# Development_Board_ATMega32.net
KiCad netlist of a schematic drawn in EAGLE
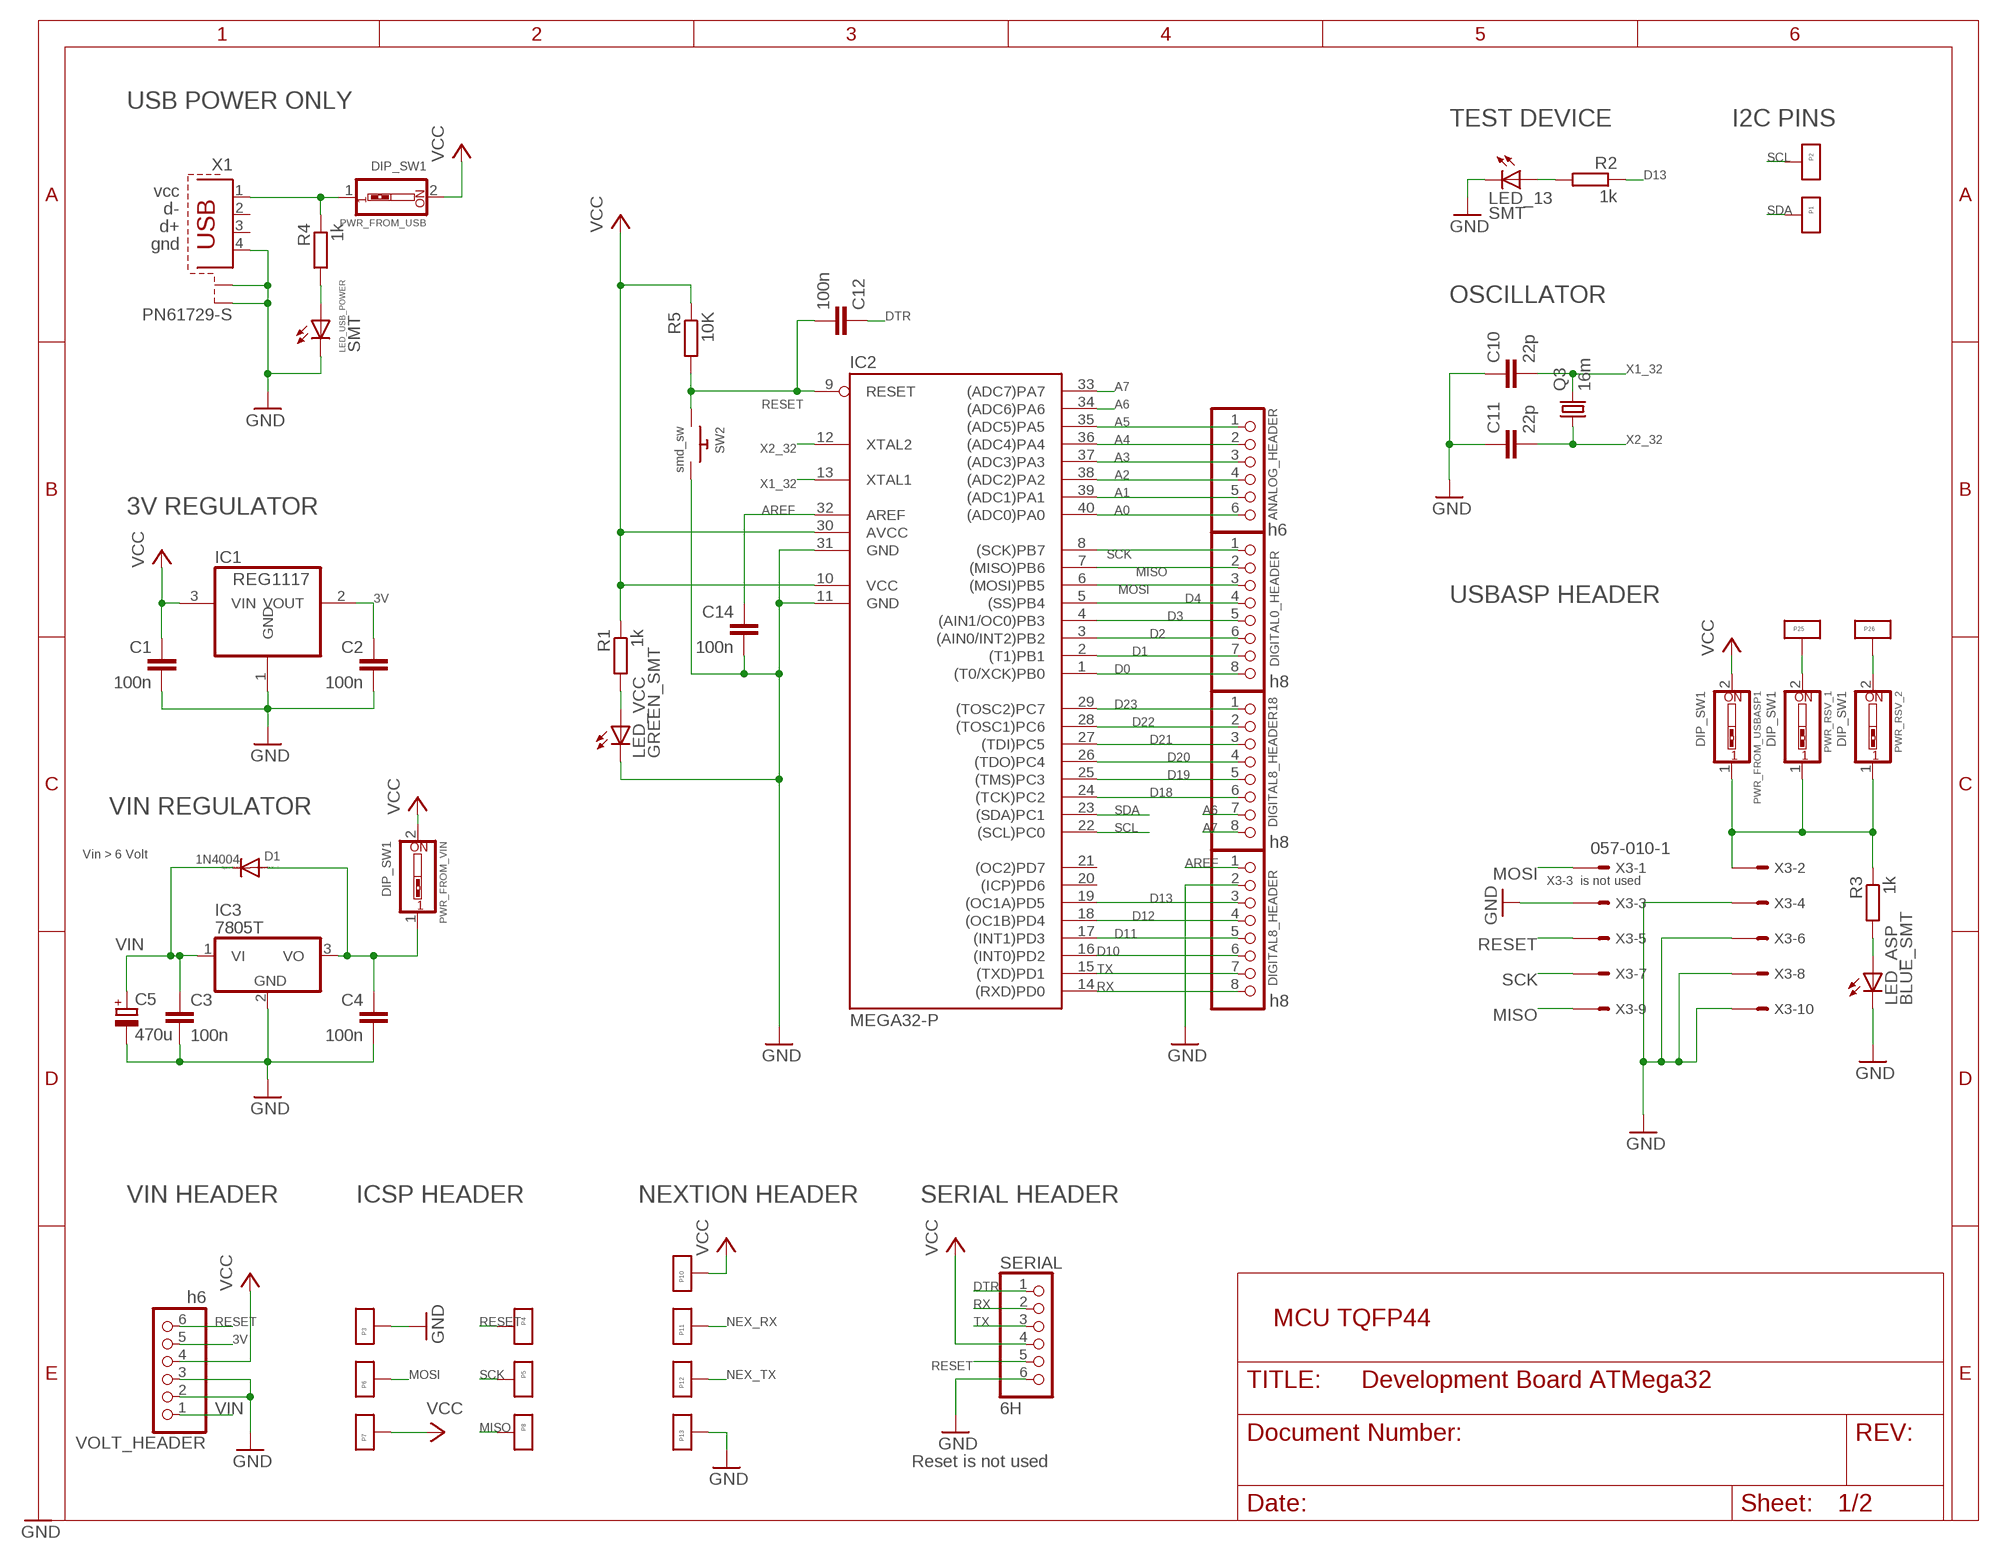
[diagram p0: schematic, sheet 1]
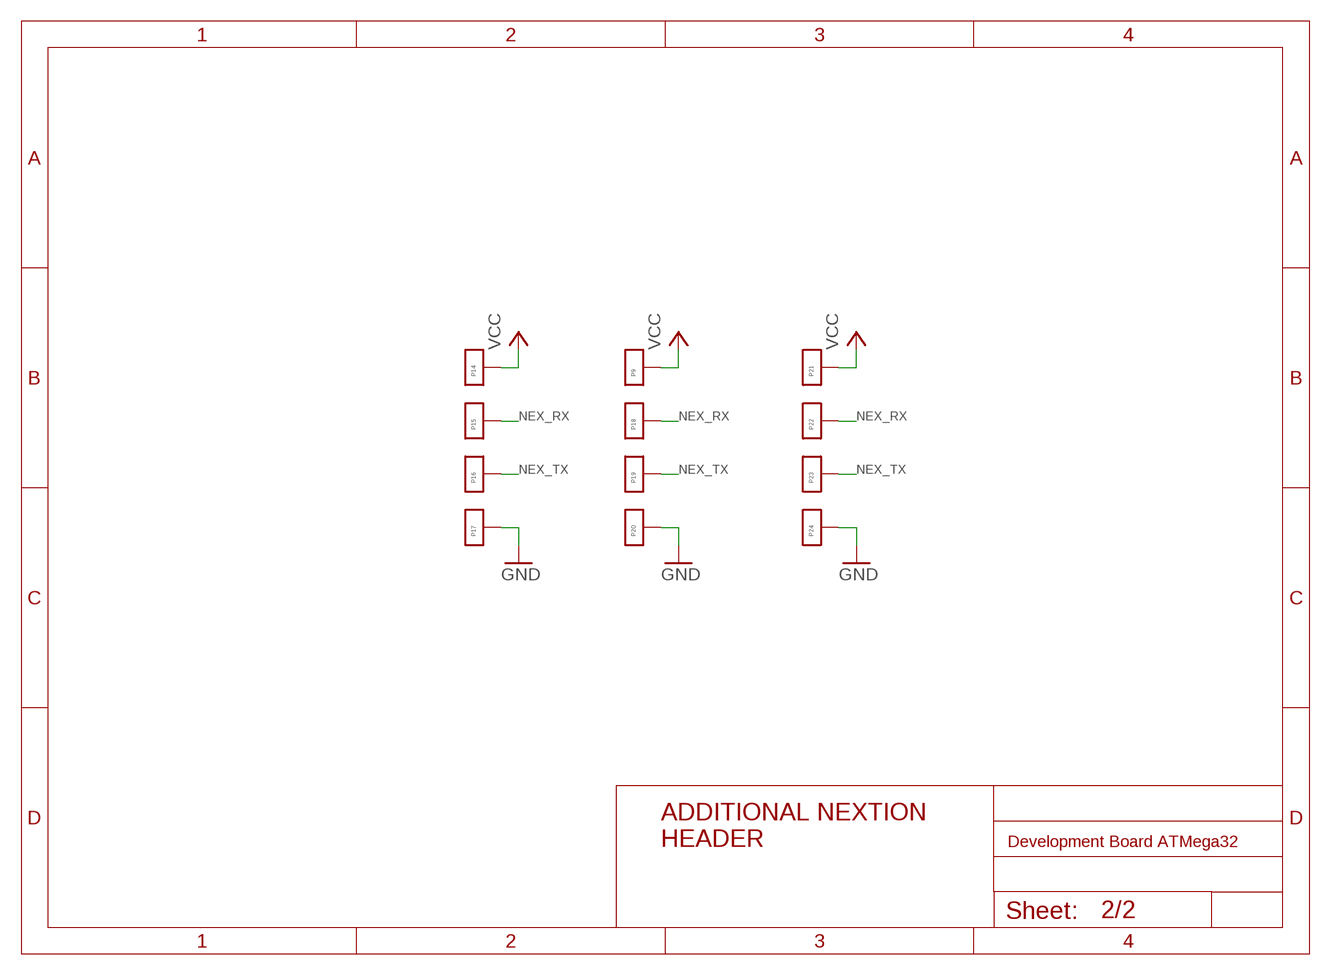
[diagram p1: schematic, sheet 2]

(export (version "E")
  (design (tool "Eeschema 10.0.6"))
  (components
    (comp (ref "P9")
      (value "PIN-BIG1X")
      (footprint "eagle-import:PIN-BIG")
      (libsource (lib "eagle-import") (part "PIN-BIG1X"))
    )
    (comp (ref "P14")
      (value "PIN-BIG1X")
      (footprint "eagle-import:PIN-BIG")
      (libsource (lib "eagle-import") (part "PIN-BIG1X"))
    )
    (comp (ref "P15")
      (value "PIN-BIG1X")
      (footprint "eagle-import:PIN-BIG")
      (libsource (lib "eagle-import") (part "PIN-BIG1X"))
    )
    (comp (ref "P16")
      (value "PIN-BIG1X")
      (footprint "eagle-import:PIN-BIG")
      (libsource (lib "eagle-import") (part "PIN-BIG1X"))
    )
    (comp (ref "P17")
      (value "PIN-BIG1X")
      (footprint "eagle-import:PIN-BIG")
      (libsource (lib "eagle-import") (part "PIN-BIG1X"))
    )
    (comp (ref "P18")
      (value "PIN-BIG1X")
      (footprint "eagle-import:PIN-BIG")
      (libsource (lib "eagle-import") (part "PIN-BIG1X"))
    )
    (comp (ref "P19")
      (value "PIN-BIG1X")
      (footprint "eagle-import:PIN-BIG")
      (libsource (lib "eagle-import") (part "PIN-BIG1X"))
    )
    (comp (ref "P20")
      (value "PIN-BIG1X")
      (footprint "eagle-import:PIN-BIG")
      (libsource (lib "eagle-import") (part "PIN-BIG1X"))
    )
    (comp (ref "P21")
      (value "PIN-BIG1X")
      (footprint "eagle-import:PIN-BIG")
      (libsource (lib "eagle-import") (part "PIN-BIG1X"))
    )
    (comp (ref "P22")
      (value "PIN-BIG1X")
      (footprint "eagle-import:PIN-BIG")
      (libsource (lib "eagle-import") (part "PIN-BIG1X"))
    )
    (comp (ref "P23")
      (value "PIN-BIG1X")
      (footprint "eagle-import:PIN-BIG")
      (libsource (lib "eagle-import") (part "PIN-BIG1X"))
    )
    (comp (ref "P24")
      (value "PIN-BIG1X")
      (footprint "eagle-import:PIN-BIG")
      (libsource (lib "eagle-import") (part "PIN-BIG1X"))
    )
    (comp (ref "ANALOG_HEADER")
      (value "h6")
      (footprint "eagle-import:1X06")
      (libsource (lib "eagle-import") (part "PINHD-1X6"))
    )
    (comp (ref "C1")
      (value "100n")
      (footprint "eagle-import:C1206")
      (libsource (lib "eagle-import") (part "C-EUC1206"))
    )
    (comp (ref "C2")
      (value "100n")
      (footprint "eagle-import:C1206")
      (libsource (lib "eagle-import") (part "C-EUC1206"))
    )
    (comp (ref "C3")
      (value "100n")
      (footprint "eagle-import:C050-025X075")
      (libsource (lib "eagle-import") (part "C-EU050-025X075"))
    )
    (comp (ref "C4")
      (value "100n")
      (footprint "eagle-import:C050-025X075")
      (libsource (lib "eagle-import") (part "C-EU050-025X075"))
    )
    (comp (ref "C5")
      (value "470u")
      (footprint "eagle-import:E5-5")
      (libsource (lib "eagle-import") (part "CPOL-EUE5-5"))
    )
    (comp (ref "C10")
      (value "22p")
      (footprint "eagle-import:C1206")
      (libsource (lib "eagle-import") (part "C-EUC1206"))
    )
    (comp (ref "C11")
      (value "22p")
      (footprint "eagle-import:C1206")
      (libsource (lib "eagle-import") (part "C-EUC1206"))
    )
    (comp (ref "C12")
      (value "100n")
      (footprint "eagle-import:C1206")
      (libsource (lib "eagle-import") (part "C-EUC1206"))
    )
    (comp (ref "C14")
      (value "100n")
      (footprint "eagle-import:C1206")
      (libsource (lib "eagle-import") (part "C-EUC1206"))
    )
    (comp (ref "D1")
      (value "1N4004")
      (footprint "eagle-import:DO41-10")
      (libsource (lib "eagle-import") (part "1N4004"))
    )
    (comp (ref "DIGITAL0_HEADER")
      (value "h8")
      (footprint "eagle-import:1X08-BIG")
      (libsource (lib "eagle-import") (part "PINHD-1X8BIG"))
    )
    (comp (ref "DIGITAL8_HEADER")
      (value "h8")
      (footprint "eagle-import:1X08-BIG")
      (libsource (lib "eagle-import") (part "PINHD-1X8BIG"))
    )
    (comp (ref "DIGITAL8_HEADER18")
      (value "h8")
      (footprint "eagle-import:1X08-BIG")
      (libsource (lib "eagle-import") (part "PINHD-1X8BIG"))
    )
    (comp (ref "IC1")
      (value "REG1117")
      (footprint "eagle-import:SOT223")
      (libsource (lib "eagle-import") (part "REG1117"))
    )
    (comp (ref "IC2")
      (value "MEGA32-P")
      (footprint "eagle-import:DIL40")
      (fields (field (name "MPN") "ATMEGA32-16PU"))
      (libsource (lib "eagle-import") (part "MEGA32-P"))
    )
    (comp (ref "IC3")
      (value "7805T")
      (footprint "eagle-import:TO220H")
      (libsource (lib "eagle-import") (part "78T05"))
    )
    (comp (ref "LED_13")
      (value "SMT")
      (footprint "eagle-import:1206")
      (libsource (lib "eagle-import") (part "LEDSMT1206"))
    )
    (comp (ref "LED_ASP")
      (value "BLUE_SMT")
      (footprint "eagle-import:1206")
      (libsource (lib "eagle-import") (part "LEDSMT1206"))
    )
    (comp (ref "LED_USB_POWER")
      (value "SMT")
      (footprint "eagle-import:1206")
      (libsource (lib "eagle-import") (part "LEDSMT1206"))
    )
    (comp (ref "LED_VCC")
      (value "GREEN_SMT")
      (footprint "eagle-import:1206")
      (libsource (lib "eagle-import") (part "LEDSMT1206"))
    )
    (comp (ref "P1")
      (value "PIN-BIG1X")
      (footprint "eagle-import:PIN-BIG")
      (libsource (lib "eagle-import") (part "PIN-BIG1X"))
    )
    (comp (ref "P2")
      (value "PIN-BIG1X")
      (footprint "eagle-import:PIN-BIG")
      (libsource (lib "eagle-import") (part "PIN-BIG1X"))
    )
    (comp (ref "P3")
      (value "PIN-BIG1X")
      (footprint "eagle-import:PIN-BIG")
      (libsource (lib "eagle-import") (part "PIN-BIG1X"))
    )
    (comp (ref "P4")
      (value "PIN-BIG1X")
      (footprint "eagle-import:PIN-BIG")
      (libsource (lib "eagle-import") (part "PIN-BIG1X"))
    )
    (comp (ref "P5")
      (value "PIN-BIG1X")
      (footprint "eagle-import:PIN-BIG")
      (libsource (lib "eagle-import") (part "PIN-BIG1X"))
    )
    (comp (ref "P6")
      (value "PIN-BIG1X")
      (footprint "eagle-import:PIN-BIG")
      (libsource (lib "eagle-import") (part "PIN-BIG1X"))
    )
    (comp (ref "P7")
      (value "PIN-BIG1X")
      (footprint "eagle-import:PIN-BIG")
      (libsource (lib "eagle-import") (part "PIN-BIG1X"))
    )
    (comp (ref "P8")
      (value "PIN-BIG1X")
      (footprint "eagle-import:PIN-BIG")
      (libsource (lib "eagle-import") (part "PIN-BIG1X"))
    )
    (comp (ref "P10")
      (value "PIN-BIG1X")
      (footprint "eagle-import:PIN-BIG")
      (libsource (lib "eagle-import") (part "PIN-BIG1X"))
    )
    (comp (ref "P11")
      (value "PIN-BIG1X")
      (footprint "eagle-import:PIN-BIG")
      (libsource (lib "eagle-import") (part "PIN-BIG1X"))
    )
    (comp (ref "P12")
      (value "PIN-BIG1X")
      (footprint "eagle-import:PIN-BIG")
      (libsource (lib "eagle-import") (part "PIN-BIG1X"))
    )
    (comp (ref "P13")
      (value "PIN-BIG1X")
      (footprint "eagle-import:PIN-BIG")
      (libsource (lib "eagle-import") (part "PIN-BIG1X"))
    )
    (comp (ref "P25")
      (value "PIN-BIG1X")
      (footprint "eagle-import:PIN-BIG")
      (libsource (lib "eagle-import") (part "PIN-BIG1X"))
    )
    (comp (ref "P26")
      (value "PIN-BIG1X")
      (footprint "eagle-import:PIN-BIG")
      (libsource (lib "eagle-import") (part "PIN-BIG1X"))
    )
    (comp (ref "PWR_FROM_USB")
      (value "DIP_SW1")
      (footprint "eagle-import:EDG-01")
      (libsource (lib "eagle-import") (part "SW_DIP-1"))
    )
    (comp (ref "PWR_FROM_USBASP1")
      (value "DIP_SW1")
      (footprint "eagle-import:EDG-01")
      (libsource (lib "eagle-import") (part "SW_DIP-1"))
    )
    (comp (ref "PWR_FROM_VIN")
      (value "DIP_SW1")
      (footprint "eagle-import:EDG-01")
      (libsource (lib "eagle-import") (part "SW_DIP-1"))
    )
    (comp (ref "PWR_RSV_1")
      (value "DIP_SW1")
      (footprint "eagle-import:EDG-01")
      (libsource (lib "eagle-import") (part "SW_DIP-1"))
    )
    (comp (ref "PWR_RSV_2")
      (value "DIP_SW1")
      (footprint "eagle-import:EDG-01")
      (libsource (lib "eagle-import") (part "SW_DIP-1"))
    )
    (comp (ref "Q3")
      (value "16m")
      (footprint "eagle-import:HC49UP")
      (libsource (lib "eagle-import") (part "CRYSTALHC49UP"))
    )
    (comp (ref "R1")
      (value "1k")
      (footprint "eagle-import:R1206")
      (libsource (lib "eagle-import") (part "R-EU_R1206"))
    )
    (comp (ref "R2")
      (value "1k")
      (footprint "eagle-import:R1206")
      (libsource (lib "eagle-import") (part "R-EU_R1206"))
    )
    (comp (ref "R3")
      (value "1k")
      (footprint "eagle-import:R1206")
      (libsource (lib "eagle-import") (part "R-EU_R1206"))
    )
    (comp (ref "R4")
      (value "1k")
      (footprint "eagle-import:R1206")
      (libsource (lib "eagle-import") (part "R-EU_R1206"))
    )
    (comp (ref "R5")
      (value "10K")
      (footprint "eagle-import:R1206")
      (libsource (lib "eagle-import") (part "R-EU_R1206"))
    )
    (comp (ref "SERIAL")
      (value "6H")
      (footprint "eagle-import:1X06")
      (libsource (lib "eagle-import") (part "PINHD-1X6"))
    )
    (comp (ref "SW2")
      (value "smd_sw")
      (footprint "eagle-import:TACT_PANA-EVQ")
      (libsource (lib "eagle-import") (part "SWITCH_PUSHBUTTONEVQ-PE"))
    )
    (comp (ref "VOLT_HEADER")
      (value "h6")
      (footprint "eagle-import:1X06")
      (libsource (lib "eagle-import") (part "PINHD-1X6"))
    )
    (comp (ref "X1")
      (value "PN61729-S")
      (footprint "eagle-import:PN61729-S")
      (libsource (lib "eagle-import") (part "PN61729-S"))
    )
    (comp (ref "X3")
      (value "057-010-1")
      (footprint "eagle-import:057-010-1")
      (libsource (lib "eagle-import") (part "057-010-1"))
    )
  )
  (nets
    (net (code "1") (name "3V") (class "Default")
      (node (ref "C2") (pin "1") (pinfunction "1_1") (pintype "passive"))
      (node (ref "IC1") (pin "2") (pinfunction "VOUT_2") (pintype "output"))
      (node (ref "VOLT_HEADER") (pin "5") (pinfunction "5_5") (pintype "passive"))
    )
    (net (code "2") (name "A0") (class "Default")
      (node (ref "ANALOG_HEADER") (pin "6") (pinfunction "6_6") (pintype "passive"))
      (node (ref "IC2") (pin "40") (pinfunction "(ADC0)PA0_40") (pintype "bidirectional"))
    )
    (net (code "3") (name "A1") (class "Default")
      (node (ref "ANALOG_HEADER") (pin "5") (pinfunction "5_5") (pintype "passive"))
      (node (ref "IC2") (pin "39") (pinfunction "(ADC1)PA1_39") (pintype "bidirectional"))
    )
    (net (code "4") (name "A2") (class "Default")
      (node (ref "ANALOG_HEADER") (pin "4") (pinfunction "4_4") (pintype "passive"))
      (node (ref "IC2") (pin "38") (pinfunction "(ADC2)PA2_38") (pintype "bidirectional"))
    )
    (net (code "5") (name "A3") (class "Default")
      (node (ref "ANALOG_HEADER") (pin "3") (pinfunction "3_3") (pintype "passive"))
      (node (ref "IC2") (pin "37") (pinfunction "(ADC3)PA3_37") (pintype "bidirectional"))
    )
    (net (code "6") (name "A4") (class "Default")
      (node (ref "ANALOG_HEADER") (pin "2") (pinfunction "2_2") (pintype "passive"))
      (node (ref "IC2") (pin "36") (pinfunction "(ADC4)PA4_36") (pintype "bidirectional"))
    )
    (net (code "7") (name "A5") (class "Default")
      (node (ref "ANALOG_HEADER") (pin "1") (pinfunction "1_1") (pintype "passive"))
      (node (ref "IC2") (pin "35") (pinfunction "(ADC5)PA5_35") (pintype "bidirectional"))
    )
    (net (code "8") (name "A6") (class "Default")
      (node (ref "DIGITAL8_HEADER18") (pin "7") (pinfunction "7_7") (pintype "passive"))
      (node (ref "IC2") (pin "34") (pinfunction "(ADC6)PA6_34") (pintype "bidirectional"))
    )
    (net (code "9") (name "A7") (class "Default")
      (node (ref "DIGITAL8_HEADER18") (pin "8") (pinfunction "8_8") (pintype "passive"))
      (node (ref "IC2") (pin "33") (pinfunction "(ADC7)PA7_33") (pintype "bidirectional"))
    )
    (net (code "10") (name "AREF") (class "Default")
      (node (ref "C14") (pin "1") (pinfunction "1_1") (pintype "passive"))
      (node (ref "DIGITAL8_HEADER") (pin "1") (pinfunction "1_1") (pintype "passive"))
      (node (ref "IC2") (pin "32") (pinfunction "AREF_32") (pintype "passive"))
    )
    (net (code "11") (name "D0") (class "Default")
      (node (ref "DIGITAL0_HEADER") (pin "8") (pinfunction "8_8") (pintype "passive"))
      (node (ref "IC2") (pin "1") (pinfunction "(T0/XCK)PB0_1") (pintype "bidirectional"))
    )
    (net (code "12") (name "D1") (class "Default")
      (node (ref "DIGITAL0_HEADER") (pin "7") (pinfunction "7_7") (pintype "passive"))
      (node (ref "IC2") (pin "2") (pinfunction "(T1)PB1_2") (pintype "bidirectional"))
    )
    (net (code "13") (name "D2") (class "Default")
      (node (ref "DIGITAL0_HEADER") (pin "6") (pinfunction "6_6") (pintype "passive"))
      (node (ref "IC2") (pin "3") (pinfunction "(AIN0/INT2)PB2_3") (pintype "bidirectional"))
    )
    (net (code "14") (name "D3") (class "Default")
      (node (ref "DIGITAL0_HEADER") (pin "5") (pinfunction "5_5") (pintype "passive"))
      (node (ref "IC2") (pin "4") (pinfunction "(AIN1/OC0)PB3_4") (pintype "bidirectional"))
    )
    (net (code "15") (name "D4") (class "Default")
      (node (ref "DIGITAL0_HEADER") (pin "4") (pinfunction "4_4") (pintype "passive"))
      (node (ref "IC2") (pin "5") (pinfunction "(SS)PB4_5") (pintype "bidirectional"))
    )
    (net (code "16") (name "D10") (class "Default")
      (node (ref "DIGITAL8_HEADER") (pin "6") (pinfunction "6_6") (pintype "passive"))
      (node (ref "IC2") (pin "16") (pinfunction "(INT0)PD2_16") (pintype "bidirectional"))
    )
    (net (code "17") (name "D11") (class "Default")
      (node (ref "DIGITAL8_HEADER") (pin "5") (pinfunction "5_5") (pintype "passive"))
      (node (ref "IC2") (pin "17") (pinfunction "(INT1)PD3_17") (pintype "bidirectional"))
    )
    (net (code "18") (name "D12") (class "Default")
      (node (ref "DIGITAL8_HEADER") (pin "4") (pinfunction "4_4") (pintype "passive"))
      (node (ref "IC2") (pin "18") (pinfunction "(OC1B)PD4_18") (pintype "bidirectional"))
    )
    (net (code "19") (name "D13") (class "Default")
      (node (ref "DIGITAL8_HEADER") (pin "3") (pinfunction "3_3") (pintype "passive"))
      (node (ref "IC2") (pin "19") (pinfunction "(OC1A)PD5_19") (pintype "bidirectional"))
      (node (ref "R2") (pin "1") (pinfunction "1_1") (pintype "passive"))
    )
    (net (code "20") (name "D18") (class "Default")
      (node (ref "DIGITAL8_HEADER18") (pin "6") (pinfunction "6_6") (pintype "passive"))
      (node (ref "IC2") (pin "24") (pinfunction "(TCK)PC2_24") (pintype "bidirectional"))
    )
    (net (code "21") (name "D19") (class "Default")
      (node (ref "DIGITAL8_HEADER18") (pin "5") (pinfunction "5_5") (pintype "passive"))
      (node (ref "IC2") (pin "25") (pinfunction "(TMS)PC3_25") (pintype "bidirectional"))
    )
    (net (code "22") (name "D20") (class "Default")
      (node (ref "DIGITAL8_HEADER18") (pin "4") (pinfunction "4_4") (pintype "passive"))
      (node (ref "IC2") (pin "26") (pinfunction "(TDO)PC4_26") (pintype "bidirectional"))
    )
    (net (code "23") (name "D21") (class "Default")
      (node (ref "DIGITAL8_HEADER18") (pin "3") (pinfunction "3_3") (pintype "passive"))
      (node (ref "IC2") (pin "27") (pinfunction "(TDI)PC5_27") (pintype "bidirectional"))
    )
    (net (code "24") (name "D22") (class "Default")
      (node (ref "DIGITAL8_HEADER18") (pin "2") (pinfunction "2_2") (pintype "passive"))
      (node (ref "IC2") (pin "28") (pinfunction "(TOSC1)PC6_28") (pintype "bidirectional"))
    )
    (net (code "25") (name "D23") (class "Default")
      (node (ref "DIGITAL8_HEADER18") (pin "1") (pinfunction "1_1") (pintype "passive"))
      (node (ref "IC2") (pin "29") (pinfunction "(TOSC2)PC7_29") (pintype "bidirectional"))
    )
    (net (code "26") (name "DTR") (class "Default")
      (node (ref "C12") (pin "1") (pinfunction "1_1") (pintype "passive"))
      (node (ref "SERIAL") (pin "1") (pinfunction "1_1") (pintype "passive"))
    )
    (net (code "27") (name "GND") (class "Default")
      (node (ref "C1") (pin "2") (pinfunction "2_2") (pintype "passive"))
      (node (ref "C10") (pin "1") (pinfunction "1_1") (pintype "passive"))
      (node (ref "C11") (pin "1") (pinfunction "1_1") (pintype "passive"))
      (node (ref "C14") (pin "2") (pinfunction "2_2") (pintype "passive"))
      (node (ref "C2") (pin "2") (pinfunction "2_2") (pintype "passive"))
      (node (ref "C3") (pin "2") (pinfunction "2_2") (pintype "passive"))
      (node (ref "C4") (pin "2") (pinfunction "2_2") (pintype "passive"))
      (node (ref "C5") (pin "-") (pinfunction "-_-") (pintype "passive"))
      (node (ref "DIGITAL8_HEADER") (pin "2") (pinfunction "2_2") (pintype "passive"))
      (node (ref "IC1") (pin "1") (pinfunction "GND_1") (pintype "power_in"))
      (node (ref "IC2") (pin "11") (pinfunction "GND_11") (pintype "power_in"))
      (node (ref "IC2") (pin "31") (pinfunction "GND_31") (pintype "power_in"))
      (node (ref "IC3") (pin "2") (pinfunction "GND_2") (pintype "passive"))
      (node (ref "LED_13") (pin "C") (pinfunction "C_C") (pintype "passive"))
      (node (ref "LED_ASP") (pin "C") (pinfunction "C_C") (pintype "passive"))
      (node (ref "LED_USB_POWER") (pin "C") (pinfunction "C_C") (pintype "passive"))
      (node (ref "LED_VCC") (pin "C") (pinfunction "C_C") (pintype "passive"))
      (node (ref "P13") (pin "P$1") (pinfunction "P$1_P$1") (pintype "bidirectional"))
      (node (ref "P17") (pin "P$1") (pinfunction "P$1_P$1") (pintype "bidirectional"))
      (node (ref "P20") (pin "P$1") (pinfunction "P$1_P$1") (pintype "bidirectional"))
      (node (ref "P24") (pin "P$1") (pinfunction "P$1_P$1") (pintype "bidirectional"))
      (node (ref "P3") (pin "P$1") (pinfunction "P$1_P$1") (pintype "bidirectional"))
      (node (ref "SERIAL") (pin "6") (pinfunction "6_6") (pintype "passive"))
      (node (ref "SW2") (pin "P$2") (pinfunction "P$2_P$2") (pintype "passive"))
      (node (ref "VOLT_HEADER") (pin "2") (pinfunction "2_2") (pintype "passive"))
      (node (ref "VOLT_HEADER") (pin "3") (pinfunction "3_3") (pintype "passive"))
      (node (ref "X1") (pin "4") (pinfunction "4_4") (pintype "passive"))
      (node (ref "X1") (pin "S1") (pinfunction "S1_S1") (pintype "passive"))
      (node (ref "X1") (pin "S2") (pinfunction "S2_S2") (pintype "passive"))
      (node (ref "X3") (pin "10") (pinfunction "S_10") (pintype "passive"))
      (node (ref "X3") (pin "3") (pinfunction "S_3") (pintype "passive"))
      (node (ref "X3") (pin "4") (pinfunction "S_4") (pintype "passive"))
      (node (ref "X3") (pin "6") (pinfunction "S_6") (pintype "passive"))
      (node (ref "X3") (pin "8") (pinfunction "S_8") (pintype "passive"))
    )
    (net (code "28") (name "MISO") (class "Default")
      (node (ref "DIGITAL0_HEADER") (pin "2") (pinfunction "2_2") (pintype "passive"))
      (node (ref "IC2") (pin "7") (pinfunction "(MISO)PB6_7") (pintype "bidirectional"))
      (node (ref "P8") (pin "P$1") (pinfunction "P$1_P$1") (pintype "bidirectional"))
      (node (ref "X3") (pin "9") (pinfunction "S_9") (pintype "passive"))
    )
    (net (code "29") (name "MOSI") (class "Default")
      (node (ref "DIGITAL0_HEADER") (pin "3") (pinfunction "3_3") (pintype "passive"))
      (node (ref "IC2") (pin "6") (pinfunction "(MOSI)PB5_6") (pintype "bidirectional"))
      (node (ref "P6") (pin "P$1") (pinfunction "P$1_P$1") (pintype "bidirectional"))
      (node (ref "X3") (pin "1") (pinfunction "S_1") (pintype "passive"))
    )
    (net (code "30") (name "NEX_RX") (class "Default")
      (node (ref "P11") (pin "P$1") (pinfunction "P$1_P$1") (pintype "bidirectional"))
      (node (ref "P15") (pin "P$1") (pinfunction "P$1_P$1") (pintype "bidirectional"))
      (node (ref "P18") (pin "P$1") (pinfunction "P$1_P$1") (pintype "bidirectional"))
      (node (ref "P22") (pin "P$1") (pinfunction "P$1_P$1") (pintype "bidirectional"))
    )
    (net (code "31") (name "NEX_TX") (class "Default")
      (node (ref "P12") (pin "P$1") (pinfunction "P$1_P$1") (pintype "bidirectional"))
      (node (ref "P16") (pin "P$1") (pinfunction "P$1_P$1") (pintype "bidirectional"))
      (node (ref "P19") (pin "P$1") (pinfunction "P$1_P$1") (pintype "bidirectional"))
      (node (ref "P23") (pin "P$1") (pinfunction "P$1_P$1") (pintype "bidirectional"))
    )
    (net (code "32") (name "Net-(IC3-VO)") (class "Default")
      (node (ref "C4") (pin "1") (pinfunction "1_1") (pintype "passive"))
      (node (ref "D1") (pin "A") (pinfunction "A_A") (pintype "passive"))
      (node (ref "IC3") (pin "3") (pinfunction "VO_3") (pintype "passive"))
      (node (ref "PWR_FROM_VIN") (pin "1") (pinfunction "1_1") (pintype "passive"))
    )
    (net (code "33") (name "Net-(LED_13-PadA)") (class "Default")
      (node (ref "LED_13") (pin "A") (pinfunction "A_A") (pintype "passive"))
      (node (ref "R2") (pin "2") (pinfunction "2_2") (pintype "passive"))
    )
    (net (code "34") (name "Net-(LED_ASP-PadA)") (class "Default")
      (node (ref "LED_ASP") (pin "A") (pinfunction "A_A") (pintype "passive"))
      (node (ref "R3") (pin "2") (pinfunction "2_2") (pintype "passive"))
    )
    (net (code "35") (name "Net-(LED_USB_POWER-PadA)") (class "Default")
      (node (ref "LED_USB_POWER") (pin "A") (pinfunction "A_A") (pintype "passive"))
      (node (ref "R4") (pin "2") (pinfunction "2_2") (pintype "passive"))
    )
    (net (code "36") (name "Net-(LED_VCC-PadA)") (class "Default")
      (node (ref "LED_VCC") (pin "A") (pinfunction "A_A") (pintype "passive"))
      (node (ref "R1") (pin "2") (pinfunction "2_2") (pintype "passive"))
    )
    (net (code "37") (name "Net-(P25-PadP$1)") (class "Default")
      (node (ref "P25") (pin "P$1") (pinfunction "P$1_P$1") (pintype "bidirectional"))
      (node (ref "PWR_RSV_1") (pin "2") (pinfunction "2_2") (pintype "passive"))
    )
    (net (code "38") (name "Net-(P26-PadP$1)") (class "Default")
      (node (ref "P26") (pin "P$1") (pinfunction "P$1_P$1") (pintype "bidirectional"))
      (node (ref "PWR_RSV_2") (pin "2") (pinfunction "2_2") (pintype "passive"))
    )
    (net (code "39") (name "Net-(PWR_FROM_USB-Pad1)") (class "Default")
      (node (ref "PWR_FROM_USB") (pin "1") (pinfunction "1_1") (pintype "passive"))
      (node (ref "R4") (pin "1") (pinfunction "1_1") (pintype "passive"))
      (node (ref "X1") (pin "1") (pinfunction "1_1") (pintype "passive"))
    )
    (net (code "40") (name "Net-(X3C-S)") (class "Default")
      (node (ref "PWR_FROM_USBASP1") (pin "1") (pinfunction "1_1") (pintype "passive"))
      (node (ref "PWR_RSV_1") (pin "1") (pinfunction "1_1") (pintype "passive"))
      (node (ref "PWR_RSV_2") (pin "1") (pinfunction "1_1") (pintype "passive"))
      (node (ref "R3") (pin "1") (pinfunction "1_1") (pintype "passive"))
      (node (ref "X3") (pin "2") (pinfunction "S_2") (pintype "passive"))
    )
    (net (code "41") (name "RESET") (class "Default")
      (node (ref "C12") (pin "2") (pinfunction "2_2") (pintype "passive"))
      (node (ref "IC2") (pin "9") (pinfunction "RESET_9") (pintype "input"))
      (node (ref "P4") (pin "P$1") (pinfunction "P$1_P$1") (pintype "bidirectional"))
      (node (ref "R5") (pin "2") (pinfunction "2_2") (pintype "passive"))
      (node (ref "SERIAL") (pin "5") (pinfunction "5_5") (pintype "passive"))
      (node (ref "SW2") (pin "P$1") (pinfunction "P$1_P$1") (pintype "passive"))
      (node (ref "VOLT_HEADER") (pin "6") (pinfunction "6_6") (pintype "passive"))
      (node (ref "X3") (pin "5") (pinfunction "S_5") (pintype "passive"))
    )
    (net (code "42") (name "RX") (class "Default")
      (node (ref "DIGITAL8_HEADER") (pin "8") (pinfunction "8_8") (pintype "passive"))
      (node (ref "IC2") (pin "14") (pinfunction "(RXD)PD0_14") (pintype "bidirectional"))
      (node (ref "SERIAL") (pin "2") (pinfunction "2_2") (pintype "passive"))
    )
    (net (code "43") (name "SCK") (class "Default")
      (node (ref "DIGITAL0_HEADER") (pin "1") (pinfunction "1_1") (pintype "passive"))
      (node (ref "IC2") (pin "8") (pinfunction "(SCK)PB7_8") (pintype "bidirectional"))
      (node (ref "P5") (pin "P$1") (pinfunction "P$1_P$1") (pintype "bidirectional"))
      (node (ref "X3") (pin "7") (pinfunction "S_7") (pintype "passive"))
    )
    (net (code "44") (name "SCL") (class "Default")
      (node (ref "IC2") (pin "22") (pinfunction "(SCL)PC0_22") (pintype "bidirectional"))
      (node (ref "P2") (pin "P$1") (pinfunction "P$1_P$1") (pintype "bidirectional"))
    )
    (net (code "45") (name "SDA") (class "Default")
      (node (ref "IC2") (pin "23") (pinfunction "(SDA)PC1_23") (pintype "bidirectional"))
      (node (ref "P1") (pin "P$1") (pinfunction "P$1_P$1") (pintype "bidirectional"))
    )
    (net (code "46") (name "TX") (class "Default")
      (node (ref "DIGITAL8_HEADER") (pin "7") (pinfunction "7_7") (pintype "passive"))
      (node (ref "IC2") (pin "15") (pinfunction "(TXD)PD1_15") (pintype "bidirectional"))
      (node (ref "SERIAL") (pin "3") (pinfunction "3_3") (pintype "passive"))
    )
    (net (code "47") (name "VCC") (class "Default")
      (node (ref "C1") (pin "1") (pinfunction "1_1") (pintype "passive"))
      (node (ref "IC1") (pin "3") (pinfunction "VIN_3") (pintype "input"))
      (node (ref "IC2") (pin "10") (pinfunction "VCC_10") (pintype "power_in"))
      (node (ref "IC2") (pin "30") (pinfunction "AVCC_30") (pintype "power_in"))
      (node (ref "P10") (pin "P$1") (pinfunction "P$1_P$1") (pintype "bidirectional"))
      (node (ref "P14") (pin "P$1") (pinfunction "P$1_P$1") (pintype "bidirectional"))
      (node (ref "P21") (pin "P$1") (pinfunction "P$1_P$1") (pintype "bidirectional"))
      (node (ref "P7") (pin "P$1") (pinfunction "P$1_P$1") (pintype "bidirectional"))
      (node (ref "P9") (pin "P$1") (pinfunction "P$1_P$1") (pintype "bidirectional"))
      (node (ref "PWR_FROM_USB") (pin "2") (pinfunction "2_2") (pintype "passive"))
      (node (ref "PWR_FROM_USBASP1") (pin "2") (pinfunction "2_2") (pintype "passive"))
      (node (ref "PWR_FROM_VIN") (pin "2") (pinfunction "2_2") (pintype "passive"))
      (node (ref "R1") (pin "1") (pinfunction "1_1") (pintype "passive"))
      (node (ref "R5") (pin "1") (pinfunction "1_1") (pintype "passive"))
      (node (ref "SERIAL") (pin "4") (pinfunction "4_4") (pintype "passive"))
      (node (ref "VOLT_HEADER") (pin "4") (pinfunction "4_4") (pintype "passive"))
    )
    (net (code "48") (name "VIN") (class "Default")
      (node (ref "C3") (pin "1") (pinfunction "1_1") (pintype "passive"))
      (node (ref "C5") (pin "+") (pinfunction "+_+") (pintype "passive"))
      (node (ref "D1") (pin "C") (pinfunction "C_C") (pintype "passive"))
      (node (ref "IC3") (pin "1") (pinfunction "VI_1") (pintype "input"))
      (node (ref "VOLT_HEADER") (pin "1") (pinfunction "1_1") (pintype "passive"))
    )
    (net (code "49") (name "X1_32") (class "Default")
      (node (ref "C10") (pin "2") (pinfunction "2_2") (pintype "passive"))
      (node (ref "IC2") (pin "13") (pinfunction "XTAL1_13") (pintype "bidirectional"))
      (node (ref "Q3") (pin "2") (pinfunction "2_2") (pintype "passive"))
    )
    (net (code "50") (name "X2_32") (class "Default")
      (node (ref "C11") (pin "2") (pinfunction "2_2") (pintype "passive"))
      (node (ref "IC2") (pin "12") (pinfunction "XTAL2_12") (pintype "bidirectional"))
      (node (ref "Q3") (pin "1") (pinfunction "1_1") (pintype "passive"))
    )
    (net (code "51") (name "unconnected-(IC2-(ICP)PD6-Pad20)") (class "Default")
      (node (ref "IC2") (pin "20") (pinfunction "(ICP)PD6_20") (pintype "bidirectional"))
    )
    (net (code "52") (name "unconnected-(IC2-(OC2)PD7-Pad21)") (class "Default")
      (node (ref "IC2") (pin "21") (pinfunction "(OC2)PD7_21") (pintype "bidirectional"))
    )
    (net (code "53") (name "unconnected-(X1-Pad2)") (class "Default")
      (node (ref "X1") (pin "2") (pinfunction "2_2") (pintype "passive"))
    )
    (net (code "54") (name "unconnected-(X1-Pad3)") (class "Default")
      (node (ref "X1") (pin "3") (pinfunction "3_3") (pintype "passive"))
    )
  )
)
